# Digital_Part.net
KiCad netlist of a schematic drawn in Altium Designer
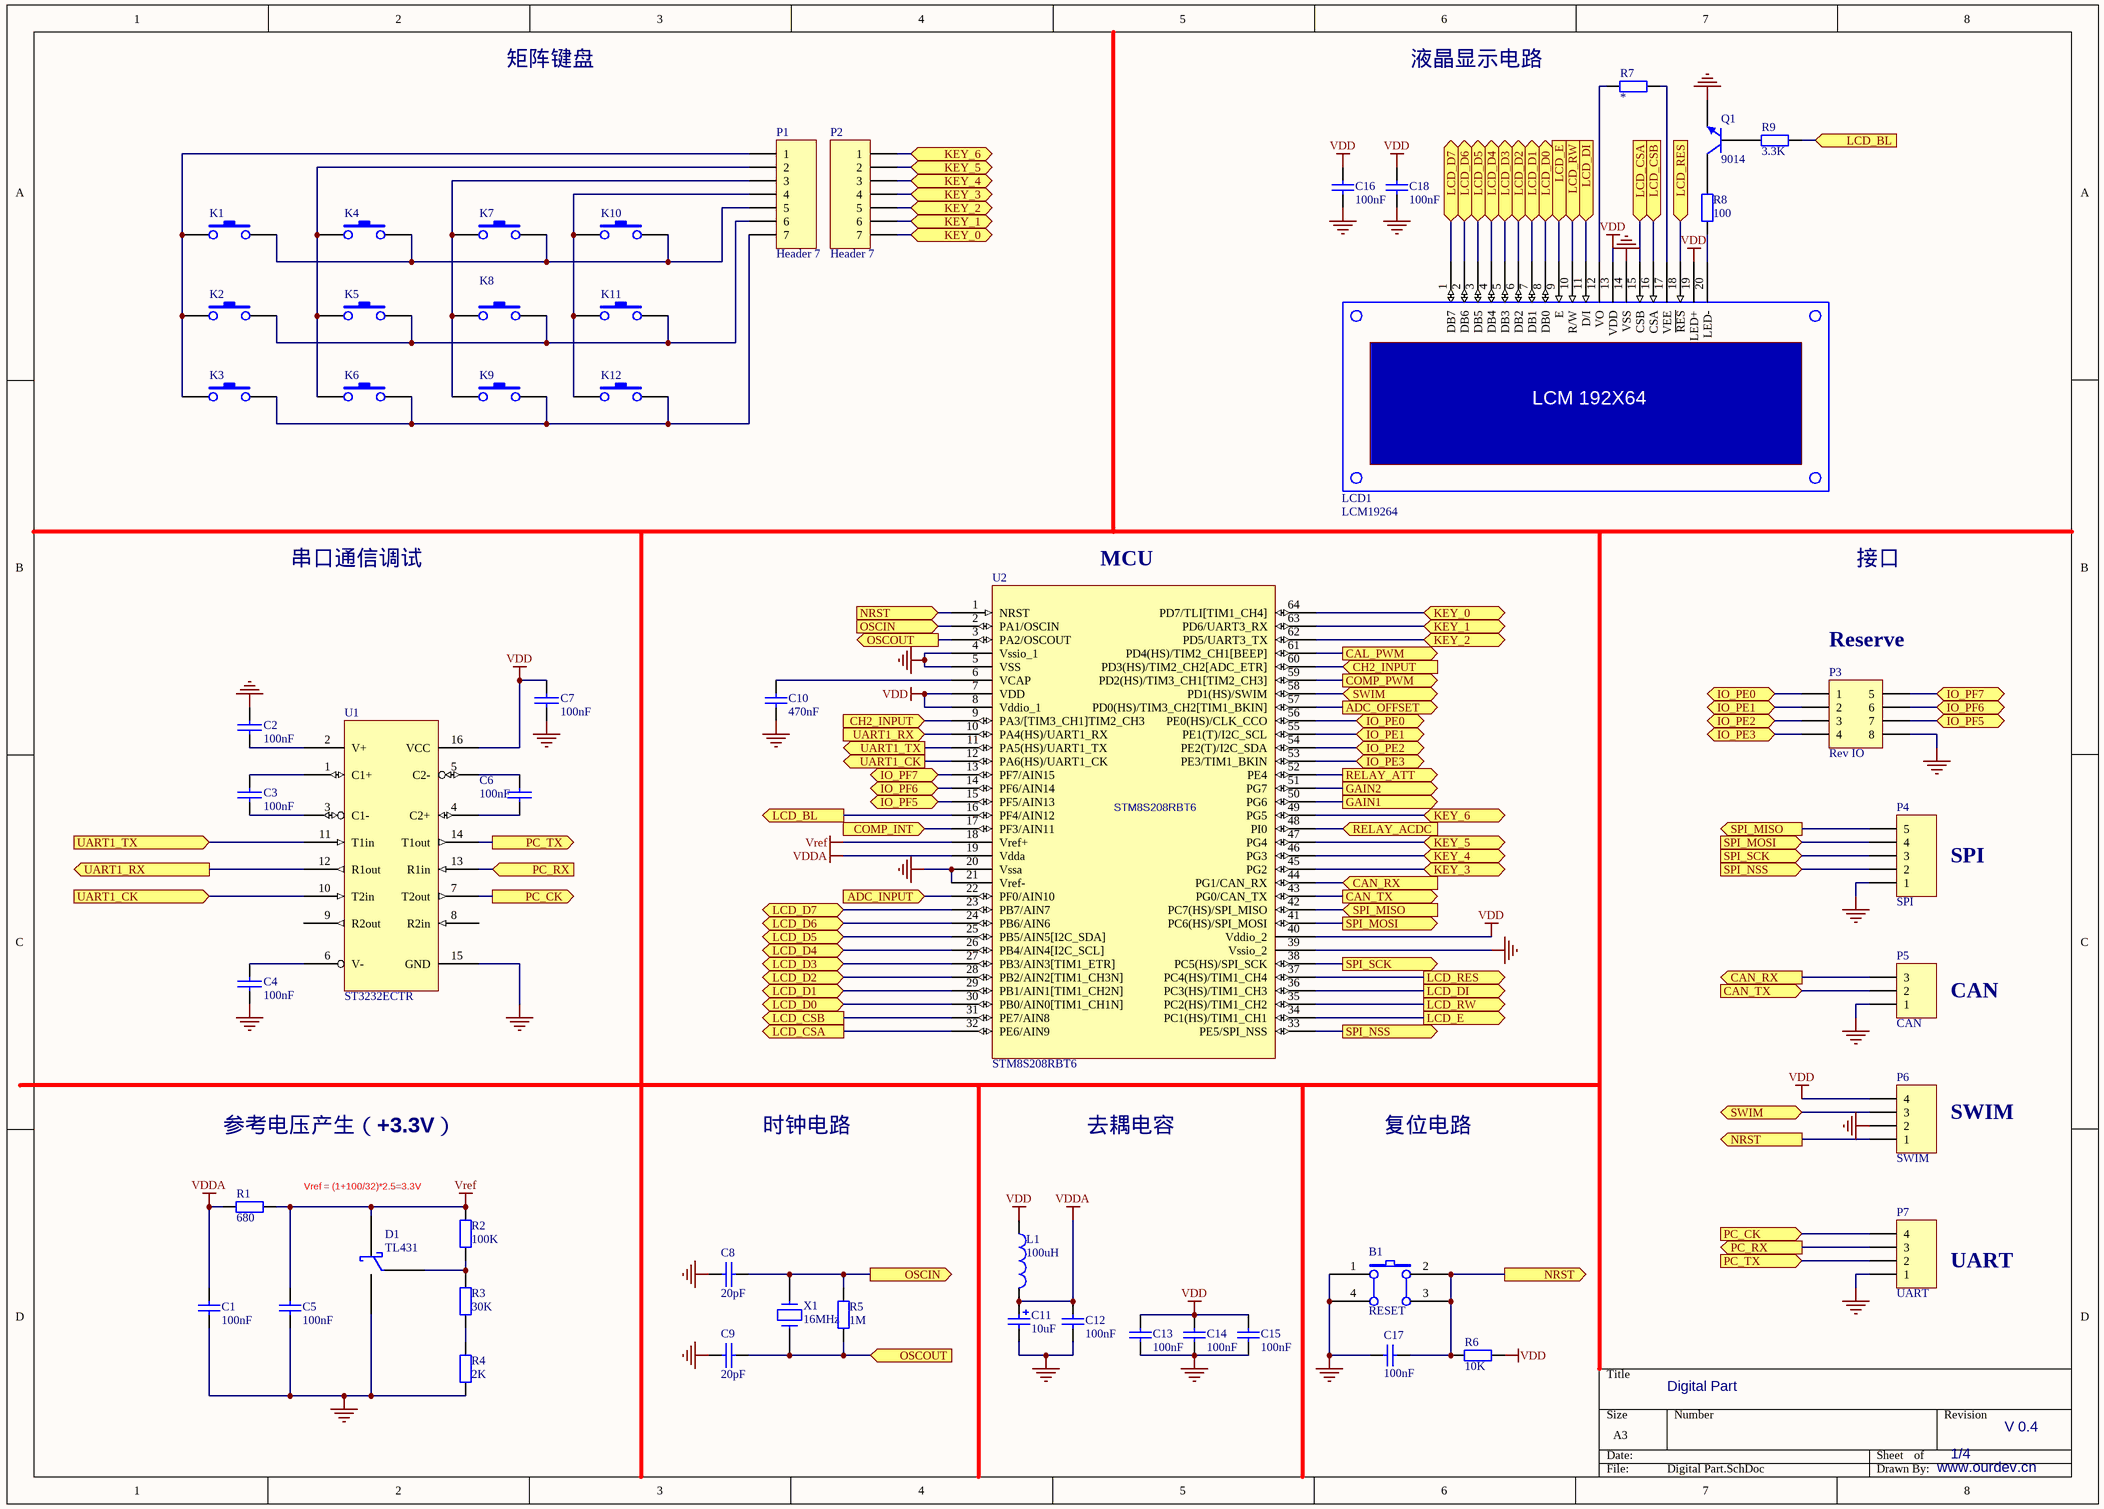
[diagram p0: Digital Part.SchDoc]

(export (version "E")
  (design (tool "Eeschema 10.0.6"))
  (components
    (comp (ref "B1")
      (value "RESET")
      (footprint "PB-2")
      (description "SE PUSHBUTTON")
      (libsource (lib "*") (part "SW PUSHBUTTON"))
    )
    (comp (ref "C1")
      (value "100nF")
      (footprint "CC2012-0805")
      (description "Capacitor")
      (fields (field (name "PUBLISHER") "Altium Limited"))
      (libsource (lib "*") (part "CAP"))
    )
    (comp (ref "C2")
      (value "100nF")
      (footprint "CC2012-0805")
      (description "Capacitor")
      (libsource (lib "") (part "CAP_1"))
    )
    (comp (ref "C3")
      (value "100nF")
      (footprint "CC2012-0805")
      (description "Capacitor")
      (libsource (lib "") (part "CAP_1"))
    )
    (comp (ref "C4")
      (value "100nF")
      (footprint "CC2012-0805")
      (description "Capacitor")
      (libsource (lib "") (part "CAP_1"))
    )
    (comp (ref "C5")
      (value "100nF")
      (footprint "CC2012-0805")
      (description "Capacitor")
      (fields (field (name "PUBLISHER") "Altium Limited"))
      (libsource (lib "*") (part "CAP"))
    )
    (comp (ref "C6")
      (value "100nF")
      (footprint "CC2012-0805")
      (description "Capacitor")
      (libsource (lib "") (part "CAP_1"))
    )
    (comp (ref "C7")
      (value "100nF")
      (footprint "CC2012-0805")
      (description "Capacitor")
      (libsource (lib "") (part "CAP_1"))
    )
    (comp (ref "C8")
      (value "20pF")
      (footprint "CC2012-0805")
      (description "Capacitor")
      (libsource (lib "") (part "CAP_1"))
    )
    (comp (ref "C9")
      (value "20pF")
      (footprint "CC2012-0805")
      (description "Capacitor")
      (libsource (lib "") (part "CAP_1"))
    )
    (comp (ref "C10")
      (value "470nF")
      (footprint "CC2012-0805")
      (description "Capacitor")
      (fields (field (name "PUBLISHER") "Altium Limited"))
      (libsource (lib "*") (part "CAP"))
    )
    (comp (ref "C11")
      (value "10uF")
      (footprint "C-1206")
      (description "Polarized Capacitor (Radial)")
      (fields (field (name "PUBLISHER") "Altium Limited"))
      (libsource (lib "*") (part "Cap Pol1"))
    )
    (comp (ref "C12")
      (value "100nF")
      (footprint "CC2012-0805")
      (description "Capacitor")
      (fields (field (name "PUBLISHER") "Altium Limited"))
      (libsource (lib "*") (part "CAP"))
    )
    (comp (ref "C13")
      (value "100nF")
      (footprint "CC2012-0805")
      (description "Capacitor")
      (fields (field (name "PUBLISHER") "Altium Limited"))
      (libsource (lib "*") (part "CAP"))
    )
    (comp (ref "C14")
      (value "100nF")
      (footprint "CC2012-0805")
      (description "Capacitor")
      (fields (field (name "PUBLISHER") "Altium Limited"))
      (libsource (lib "*") (part "CAP"))
    )
    (comp (ref "C15")
      (value "100nF")
      (footprint "CC2012-0805")
      (description "Capacitor")
      (fields (field (name "PUBLISHER") "Altium Limited"))
      (libsource (lib "*") (part "CAP"))
    )
    (comp (ref "C16")
      (value "100nF")
      (footprint "CC2012-0805")
      (description "Capacitor")
      (fields (field (name "PUBLISHER") "Altium Limited"))
      (libsource (lib "*") (part "CAP"))
    )
    (comp (ref "C17")
      (value "100nF")
      (footprint "CC2012-0805")
      (description "Capacitor")
      (fields (field (name "PUBLISHER") "Altium Limited"))
      (libsource (lib "*") (part "CAP"))
    )
    (comp (ref "C18")
      (value "100nF")
      (footprint "CC2012-0805")
      (description "Capacitor")
      (fields (field (name "PUBLISHER") "Altium Limited"))
      (libsource (lib "*") (part "CAP"))
    )
    (comp (ref "D1") (value "TL431") (footprint "SOT-89") (libsource (lib "TL431") (part "TL431")))
    (comp (ref "K1") (value "~") (footprint "PB-2") (libsource (lib "*") (part "SW-PB")))
    (comp (ref "K2") (value "~") (footprint "PB-2") (libsource (lib "*") (part "SW-PB")))
    (comp (ref "K3") (value "~") (footprint "PB-2") (libsource (lib "*") (part "SW-PB")))
    (comp (ref "K4") (value "~") (footprint "PB-2") (libsource (lib "*") (part "SW-PB")))
    (comp (ref "K5") (value "~") (footprint "PB-2") (libsource (lib "*") (part "SW-PB")))
    (comp (ref "K6") (value "~") (footprint "PB-2") (libsource (lib "*") (part "SW-PB")))
    (comp (ref "K7") (value "~") (footprint "PB-2") (libsource (lib "*") (part "SW-PB")))
    (comp (ref "K8") (value "~") (footprint "PB-2") (libsource (lib "*") (part "SW-PB")))
    (comp (ref "K9") (value "~") (footprint "PB-2") (libsource (lib "*") (part "SW-PB")))
    (comp (ref "K10") (value "~") (footprint "PB-2") (libsource (lib "*") (part "SW-PB")))
    (comp (ref "K11") (value "~") (footprint "PB-2") (libsource (lib "*") (part "SW-PB")))
    (comp (ref "K12") (value "~") (footprint "PB-2") (libsource (lib "*") (part "SW-PB")))
    (comp (ref "L1")
      (value "100uH")
      (footprint "L-1206")
      (description "Inductor")
      (fields (field (name "PUBLISHER") "Altium Limited"))
      (libsource (lib "*") (part "Inductor"))
    )
    (comp (ref "LCD1")
      (value "LCM19264")
      (footprint "HDR2X10")
      (libsource (lib "LCM 19264") (part "LCM19264"))
    )
    (comp (ref "P1")
      (value "Header 7")
      (footprint "HDR1X7")
      (description "Header, 7-Pin")
      (fields (field (name "PUBLISHER") "Altium Limited"))
      (libsource (lib "") (part "Header 7_1"))
    )
    (comp (ref "P2")
      (value "Header 7")
      (footprint "HDR1X7")
      (description "Header, 7-Pin")
      (fields (field (name "PUBLISHER") "Altium Limited"))
      (libsource (lib "Miscellaneous Connectors") (part "Header 7"))
    )
    (comp (ref "P3")
      (value "Rev IO")
      (footprint "HDR2X4_CEN")
      (description "Header, 4-Pin, Dual row")
      (fields (field (name "PUBLISHER") "Altium Limited"))
      (libsource (lib "Miscellaneous Connectors") (part "Header 4X2A"))
    )
    (comp (ref "P4")
      (value "SPI")
      (footprint "HDR1X5")
      (description "Header, 5-Pin")
      (fields (field (name "PUBLISHER") "Altium Limited"))
      (libsource (lib "Miscellaneous Connectors") (part "Header 5"))
    )
    (comp (ref "P5")
      (value "CAN")
      (footprint "HDR1X3")
      (description "Header, 3-Pin")
      (fields (field (name "PUBLISHER") "Altium Limited"))
      (libsource (lib "Miscellaneous Connectors") (part "Header 3"))
    )
    (comp (ref "P6")
      (value "SWIM")
      (footprint "HDR1X4")
      (description "Header, 4-Pin")
      (fields (field (name "PUBLISHER") "Altium Limited"))
      (libsource (lib "Miscellaneous Connectors") (part "Header 4"))
    )
    (comp (ref "P7")
      (value "UART")
      (footprint "HDR1X4")
      (description "Header, 4-Pin")
      (fields (field (name "PUBLISHER") "Altium Limited"))
      (libsource (lib "Miscellaneous Connectors") (part "Header 4"))
    )
    (comp (ref "Q1")
      (value "9014")
      (footprint "SOT-23")
      (description "NPN General Purpose Amplifier")
      (fields (field (name "PUBLISHER") "Altium Limited"))
      (libsource (lib "Miscellaneous Devices") (part "2N3904"))
    )
    (comp (ref "R1")
      (value "680")
      (footprint "CR2012-0805")
      (description "Resistor")
      (fields (field (name "PUBLISHER") "Altium Limited"))
      (libsource (lib "") (part "Res2_2"))
    )
    (comp (ref "R2")
      (value "100K")
      (footprint "CR2012-0805")
      (description "Resistor")
      (fields (field (name "PUBLISHER") "Altium Limited"))
      (libsource (lib "") (part "Res2_1"))
    )
    (comp (ref "R3")
      (value "30K")
      (footprint "CR2012-0805")
      (description "Resistor")
      (fields (field (name "PUBLISHER") "Altium Limited"))
      (libsource (lib "") (part "Res2_1"))
    )
    (comp (ref "R4")
      (value "2K")
      (footprint "CR2012-0805")
      (description "Resistor")
      (fields (field (name "PUBLISHER") "Altium Limited"))
      (libsource (lib "") (part "Res2_1"))
    )
    (comp (ref "R5")
      (value "1M")
      (footprint "CR2012-0805")
      (description "Resistor")
      (fields (field (name "PUBLISHER") "Altium Limited"))
      (libsource (lib "") (part "Res2_3"))
    )
    (comp (ref "R6")
      (value "10K")
      (footprint "CR2012-0805")
      (description "Resistor")
      (fields (field (name "PUBLISHER") "Altium Limited"))
      (libsource (lib "Miscellaneous Devices") (part "Res2"))
    )
    (comp (ref "R7")
      (value "*")
      (footprint "CR2012-0805")
      (description "Resistor")
      (fields (field (name "ALTIUM_VALUE") "*") (field (name "PUBLISHER") "Altium Limited"))
      (libsource (lib "") (part "Res2_2"))
    )
    (comp (ref "R8")
      (value "100")
      (footprint "CR2012-0805")
      (description "Resistor")
      (fields (field (name "Comment") "3.3K") (field (name "PUBLISHER") "Altium Limited"))
      (libsource (lib "") (part "Res2_1"))
    )
    (comp (ref "R9")
      (value "3.3K")
      (footprint "CR2012-0805")
      (description "Resistor")
      (fields (field (name "PUBLISHER") "Altium Limited"))
      (libsource (lib "Miscellaneous Devices") (part "Res2"))
    )
    (comp (ref "U1")
      (value "ST3232ECTR")
      (footprint "SO-16")
      (description "3.3V/5V Dual RS232 Transceiver w/ Int. Cap.")
      (libsource (lib "*") (part "ST3232"))
    )
    (comp (ref "U2")
      (value "STM8S208RBT6")
      (footprint "TQFP-64")
      (libsource (lib "STM8S208RBT6") (part "STM8S208RBT6"))
    )
    (comp (ref "X1")
      (value "16MHz")
      (footprint "CRYSTAL")
      (description "Crystal")
      (libsource (lib "*") (part "CRYSTAL"))
    )
  )
  (nets
    (net (code "1") (name "/ADC_INPUT") (class "Default")
      (node (ref "U2") (pin "22") (pinfunction "PF0/AIN10_22") (pintype "bidirectional"))
    )
    (net (code "2") (name "/ADC_OFFSET") (class "Default")
      (node (ref "U2") (pin "57") (pinfunction "PD0(HS)/TIM3_CH2[TIM1_BKIN]_57") (pintype "bidirectional"))
    )
    (net (code "3") (name "/CAL_PWM") (class "Default")
      (node (ref "U2") (pin "61") (pinfunction "PD4(HS)/TIM2_CH1[BEEP]_61") (pintype "bidirectional"))
    )
    (net (code "4") (name "/CAN_RX") (class "Default")
      (node (ref "P5") (pin "3") (pinfunction "3_3") (pintype "passive"))
      (node (ref "U2") (pin "44") (pinfunction "PG1/CAN_RX_44") (pintype "bidirectional"))
    )
    (net (code "5") (name "/CAN_TX") (class "Default")
      (node (ref "P5") (pin "2") (pinfunction "2_2") (pintype "passive"))
      (node (ref "U2") (pin "43") (pinfunction "PG0/CAN_TX_43") (pintype "bidirectional"))
    )
    (net (code "6") (name "/CH2_INPUT") (class "Default")
      (node (ref "U2") (pin "60") (pinfunction "PD3(HS)/TIM2_CH2[ADC_ETR]_60") (pintype "bidirectional"))
      (node (ref "U2") (pin "9") (pinfunction "PA3/[TIM3_CH1]TIM2_CH3_9") (pintype "bidirectional"))
    )
    (net (code "7") (name "/COMP_INT") (class "Default")
      (node (ref "U2") (pin "17") (pinfunction "PF3/AIN11_17") (pintype "bidirectional"))
    )
    (net (code "8") (name "/COMP_PWM") (class "Default")
      (node (ref "U2") (pin "59") (pinfunction "PD2(HS)/TIM3_CH1[TIM2_CH3]_59") (pintype "bidirectional"))
    )
    (net (code "9") (name "/GAIN1") (class "Default")
      (node (ref "U2") (pin "50") (pinfunction "PG6_50") (pintype "bidirectional"))
    )
    (net (code "10") (name "/GAIN2") (class "Default")
      (node (ref "U2") (pin "51") (pinfunction "PG7_51") (pintype "bidirectional"))
    )
    (net (code "11") (name "/IO_PE0") (class "Default")
      (node (ref "P3") (pin "1") (pinfunction "1_1") (pintype "passive"))
      (node (ref "U2") (pin "56") (pinfunction "PE0(HS)/CLK_CCO_56") (pintype "bidirectional"))
    )
    (net (code "12") (name "/IO_PE1") (class "Default")
      (node (ref "P3") (pin "2") (pinfunction "2_2") (pintype "passive"))
      (node (ref "U2") (pin "55") (pinfunction "PE1(T)/I2C_SCL_55") (pintype "bidirectional"))
    )
    (net (code "13") (name "/IO_PE2") (class "Default")
      (node (ref "P3") (pin "3") (pinfunction "3_3") (pintype "passive"))
      (node (ref "U2") (pin "54") (pinfunction "PE2(T)/I2C_SDA_54") (pintype "bidirectional"))
    )
    (net (code "14") (name "/IO_PE3") (class "Default")
      (node (ref "P3") (pin "4") (pinfunction "4_4") (pintype "passive"))
      (node (ref "U2") (pin "53") (pinfunction "PE3/TIM1_BKIN_53") (pintype "bidirectional"))
    )
    (net (code "15") (name "/IO_PF5") (class "Default")
      (node (ref "P3") (pin "7") (pinfunction "7_7") (pintype "passive"))
      (node (ref "U2") (pin "15") (pinfunction "PF5/AIN13_15") (pintype "bidirectional"))
    )
    (net (code "16") (name "/IO_PF6") (class "Default")
      (node (ref "P3") (pin "6") (pinfunction "6_6") (pintype "passive"))
      (node (ref "U2") (pin "14") (pinfunction "PF6/AIN14_14") (pintype "bidirectional"))
    )
    (net (code "17") (name "/IO_PF7") (class "Default")
      (node (ref "P3") (pin "5") (pinfunction "5_5") (pintype "passive"))
      (node (ref "U2") (pin "13") (pinfunction "PF7/AIN15_13") (pintype "bidirectional"))
    )
    (net (code "18") (name "/KEY_0") (class "Default")
      (node (ref "P2") (pin "7") (pinfunction "7_7") (pintype "passive"))
      (node (ref "U2") (pin "64") (pinfunction "PD7/TLI[TIM1_CH4]_64") (pintype "bidirectional"))
    )
    (net (code "19") (name "/KEY_1") (class "Default")
      (node (ref "P2") (pin "6") (pinfunction "6_6") (pintype "passive"))
      (node (ref "U2") (pin "63") (pinfunction "PD6/UART3_RX_63") (pintype "bidirectional"))
    )
    (net (code "20") (name "/KEY_2") (class "Default")
      (node (ref "P2") (pin "5") (pinfunction "5_5") (pintype "passive"))
      (node (ref "U2") (pin "62") (pinfunction "PD5/UART3_TX_62") (pintype "bidirectional"))
    )
    (net (code "21") (name "/KEY_3") (class "Default")
      (node (ref "P2") (pin "4") (pinfunction "4_4") (pintype "passive"))
      (node (ref "U2") (pin "45") (pinfunction "PG2_45") (pintype "bidirectional"))
    )
    (net (code "22") (name "/KEY_4") (class "Default")
      (node (ref "P2") (pin "3") (pinfunction "3_3") (pintype "passive"))
      (node (ref "U2") (pin "46") (pinfunction "PG3_46") (pintype "bidirectional"))
    )
    (net (code "23") (name "/KEY_5") (class "Default")
      (node (ref "P2") (pin "2") (pinfunction "2_2") (pintype "passive"))
      (node (ref "U2") (pin "47") (pinfunction "PG4_47") (pintype "bidirectional"))
    )
    (net (code "24") (name "/KEY_6") (class "Default")
      (node (ref "P2") (pin "1") (pinfunction "1_1") (pintype "passive"))
      (node (ref "U2") (pin "49") (pinfunction "PG5_49") (pintype "bidirectional"))
    )
    (net (code "25") (name "/LCD_BL") (class "Default")
      (node (ref "R9") (pin "1") (pinfunction "1_1") (pintype "passive"))
      (node (ref "U2") (pin "16") (pinfunction "PF4/AIN12_16") (pintype "bidirectional"))
    )
    (net (code "26") (name "/LCD_CSA") (class "Default")
      (node (ref "LCD1") (pin "15") (pinfunction "CSB_15") (pintype "input"))
      (node (ref "U2") (pin "32") (pinfunction "PE6/AIN9_32") (pintype "bidirectional"))
    )
    (net (code "27") (name "/LCD_CSB") (class "Default")
      (node (ref "LCD1") (pin "16") (pinfunction "CSA_16") (pintype "input"))
      (node (ref "U2") (pin "31") (pinfunction "PE7/AIN8_31") (pintype "bidirectional"))
    )
    (net (code "28") (name "/LCD_D0") (class "Default")
      (node (ref "LCD1") (pin "8") (pinfunction "DB0_8") (pintype "bidirectional"))
      (node (ref "U2") (pin "30") (pinfunction "PB0/AIN0[TIM1_CH1N]_30") (pintype "bidirectional"))
    )
    (net (code "29") (name "/LCD_D1") (class "Default")
      (node (ref "LCD1") (pin "7") (pinfunction "DB1_7") (pintype "bidirectional"))
      (node (ref "U2") (pin "29") (pinfunction "PB1/AIN1[TIM1_CH2N]_29") (pintype "bidirectional"))
    )
    (net (code "30") (name "/LCD_D2") (class "Default")
      (node (ref "LCD1") (pin "6") (pinfunction "DB2_6") (pintype "bidirectional"))
      (node (ref "U2") (pin "28") (pinfunction "PB2/AIN2[TIM1_CH3N]_28") (pintype "bidirectional"))
    )
    (net (code "31") (name "/LCD_D3") (class "Default")
      (node (ref "LCD1") (pin "5") (pinfunction "DB3_5") (pintype "bidirectional"))
      (node (ref "U2") (pin "27") (pinfunction "PB3/AIN3[TIM1_ETR]_27") (pintype "bidirectional"))
    )
    (net (code "32") (name "/LCD_D4") (class "Default")
      (node (ref "LCD1") (pin "4") (pinfunction "DB4_4") (pintype "bidirectional"))
      (node (ref "U2") (pin "26") (pinfunction "PB4/AIN4[I2C_SCL]_26") (pintype "bidirectional"))
    )
    (net (code "33") (name "/LCD_D5") (class "Default")
      (node (ref "LCD1") (pin "3") (pinfunction "DB5_3") (pintype "bidirectional"))
      (node (ref "U2") (pin "25") (pinfunction "PB5/AIN5[I2C_SDA]_25") (pintype "bidirectional"))
    )
    (net (code "34") (name "/LCD_D6") (class "Default")
      (node (ref "LCD1") (pin "2") (pinfunction "DB6_2") (pintype "bidirectional"))
      (node (ref "U2") (pin "24") (pinfunction "PB6/AIN6_24") (pintype "bidirectional"))
    )
    (net (code "35") (name "/LCD_D7") (class "Default")
      (node (ref "LCD1") (pin "1") (pinfunction "DB7_1") (pintype "bidirectional"))
      (node (ref "U2") (pin "23") (pinfunction "PB7/AIN7_23") (pintype "bidirectional"))
    )
    (net (code "36") (name "/LCD_DI") (class "Default")
      (node (ref "LCD1") (pin "11") (pinfunction "D/I_11") (pintype "input"))
      (node (ref "U2") (pin "36") (pinfunction "PC3(HS)/TIM1_CH3_36") (pintype "bidirectional"))
    )
    (net (code "37") (name "/LCD_E") (class "Default")
      (node (ref "LCD1") (pin "9") (pinfunction "E_9") (pintype "input"))
      (node (ref "U2") (pin "34") (pinfunction "PC1(HS)/TIM1_CH1_34") (pintype "bidirectional"))
    )
    (net (code "38") (name "/LCD_RES") (class "Default")
      (node (ref "LCD1") (pin "18") (pinfunction "~{RES}_18") (pintype "input"))
      (node (ref "U2") (pin "37") (pinfunction "PC4(HS)/TIM1_CH4_37") (pintype "bidirectional"))
    )
    (net (code "39") (name "/LCD_RW") (class "Default")
      (node (ref "LCD1") (pin "10") (pinfunction "R/W_10") (pintype "input"))
      (node (ref "U2") (pin "35") (pinfunction "PC2(HS)/TIM1_CH2_35") (pintype "bidirectional"))
    )
    (net (code "40") (name "/NRST") (class "Default")
      (node (ref "B1") (pin "2") (pinfunction "B0_2") (pintype "passive"))
      (node (ref "B1") (pin "3") (pinfunction "B1_3") (pintype "passive"))
      (node (ref "C17") (pin "2") (pinfunction "2_2") (pintype "passive"))
      (node (ref "P6") (pin "1") (pinfunction "1_1") (pintype "passive"))
      (node (ref "R6") (pin "2") (pinfunction "2_2") (pintype "passive"))
      (node (ref "U2") (pin "1") (pinfunction "NRST_1") (pintype "input"))
    )
    (net (code "41") (name "/OSCIN") (class "Default")
      (node (ref "C8") (pin "1") (pinfunction "1_1") (pintype "passive"))
      (node (ref "R5") (pin "2") (pinfunction "2_2") (pintype "passive"))
      (node (ref "U2") (pin "2") (pinfunction "PA1/OSCIN_2") (pintype "bidirectional"))
      (node (ref "X1") (pin "2") (pinfunction "2_2") (pintype "passive"))
    )
    (net (code "42") (name "/OSCOUT") (class "Default")
      (node (ref "C9") (pin "1") (pinfunction "1_1") (pintype "passive"))
      (node (ref "R5") (pin "1") (pinfunction "1_1") (pintype "passive"))
      (node (ref "U2") (pin "3") (pinfunction "PA2/OSCOUT_3") (pintype "bidirectional"))
      (node (ref "X1") (pin "1") (pinfunction "1_1") (pintype "passive"))
    )
    (net (code "43") (name "/PC_CK") (class "Default")
      (node (ref "P7") (pin "4") (pinfunction "4_4") (pintype "passive"))
      (node (ref "U1") (pin "7") (pinfunction "T2out_7") (pintype "output"))
    )
    (net (code "44") (name "/PC_RX") (class "Default")
      (node (ref "P7") (pin "3") (pinfunction "3_3") (pintype "passive"))
      (node (ref "U1") (pin "13") (pinfunction "R1in_13") (pintype "input"))
    )
    (net (code "45") (name "/PC_TX") (class "Default")
      (node (ref "P7") (pin "2") (pinfunction "2_2") (pintype "passive"))
      (node (ref "U1") (pin "14") (pinfunction "T1out_14") (pintype "output"))
    )
    (net (code "46") (name "/RELAY_ACDC") (class "Default")
      (node (ref "U2") (pin "48") (pinfunction "PI0_48") (pintype "bidirectional"))
    )
    (net (code "47") (name "/RELAY_ATT") (class "Default")
      (node (ref "U2") (pin "52") (pinfunction "PE4_52") (pintype "bidirectional"))
    )
    (net (code "48") (name "/SPI_MISO") (class "Default")
      (node (ref "P4") (pin "5") (pinfunction "5_5") (pintype "passive"))
      (node (ref "U2") (pin "42") (pinfunction "PC7(HS)/SPI_MISO_42") (pintype "bidirectional"))
    )
    (net (code "49") (name "/SPI_MOSI") (class "Default")
      (node (ref "P4") (pin "4") (pinfunction "4_4") (pintype "passive"))
      (node (ref "U2") (pin "41") (pinfunction "PC6(HS)/SPI_MOSI_41") (pintype "bidirectional"))
    )
    (net (code "50") (name "/SPI_NSS") (class "Default")
      (node (ref "P4") (pin "2") (pinfunction "2_2") (pintype "passive"))
      (node (ref "U2") (pin "33") (pinfunction "PE5/SPI_NSS_33") (pintype "bidirectional"))
    )
    (net (code "51") (name "/SPI_SCK") (class "Default")
      (node (ref "P4") (pin "3") (pinfunction "3_3") (pintype "passive"))
      (node (ref "U2") (pin "38") (pinfunction "PC5(HS)/SPI_SCK_38") (pintype "bidirectional"))
    )
    (net (code "52") (name "/SWIM") (class "Default")
      (node (ref "P6") (pin "3") (pinfunction "3_3") (pintype "passive"))
      (node (ref "U2") (pin "58") (pinfunction "PD1(HS)/SWIM_58") (pintype "bidirectional"))
    )
    (net (code "53") (name "/UART1_CK") (class "Default")
      (node (ref "U1") (pin "10") (pinfunction "T2in_10") (pintype "input"))
      (node (ref "U2") (pin "12") (pinfunction "PA6(HS)/UART1_CK_12") (pintype "bidirectional"))
    )
    (net (code "54") (name "/UART1_RX") (class "Default")
      (node (ref "U1") (pin "12") (pinfunction "R1out_12") (pintype "output"))
      (node (ref "U2") (pin "10") (pinfunction "PA4(HS)/UART1_RX_10") (pintype "bidirectional"))
    )
    (net (code "55") (name "/UART1_TX") (class "Default")
      (node (ref "U1") (pin "11") (pinfunction "T1in_11") (pintype "input"))
      (node (ref "U2") (pin "11") (pinfunction "PA5(HS)/UART1_TX_11") (pintype "bidirectional"))
    )
    (net (code "56") (name "GND") (class "Default")
      (node (ref "B1") (pin "1") (pinfunction "A0_1") (pintype "passive"))
      (node (ref "B1") (pin "4") (pinfunction "A1_4") (pintype "passive"))
      (node (ref "C1") (pin "2") (pinfunction "2_2") (pintype "passive"))
      (node (ref "C10") (pin "1") (pinfunction "1_1") (pintype "passive"))
      (node (ref "C11") (pin "2") (pinfunction "1_2") (pintype "passive"))
      (node (ref "C12") (pin "2") (pinfunction "2_2") (pintype "passive"))
      (node (ref "C13") (pin "2") (pinfunction "2_2") (pintype "passive"))
      (node (ref "C14") (pin "2") (pinfunction "2_2") (pintype "passive"))
      (node (ref "C15") (pin "2") (pinfunction "2_2") (pintype "passive"))
      (node (ref "C16") (pin "2") (pinfunction "2_2") (pintype "passive"))
      (node (ref "C17") (pin "1") (pinfunction "1_1") (pintype "passive"))
      (node (ref "C18") (pin "2") (pinfunction "2_2") (pintype "passive"))
      (node (ref "C2") (pin "1") (pinfunction "1_1") (pintype "passive"))
      (node (ref "C4") (pin "1") (pinfunction "1_1") (pintype "passive"))
      (node (ref "C5") (pin "2") (pinfunction "2_2") (pintype "passive"))
      (node (ref "C7") (pin "2") (pinfunction "2_2") (pintype "passive"))
      (node (ref "C8") (pin "2") (pinfunction "2_2") (pintype "passive"))
      (node (ref "C9") (pin "2") (pinfunction "2_2") (pintype "passive"))
      (node (ref "D1") (pin "2") (pinfunction "ANODE_2") (pintype "passive"))
      (node (ref "LCD1") (pin "14") (pinfunction "VSS_14") (pintype "power_in"))
      (node (ref "P3") (pin "8") (pinfunction "8_8") (pintype "passive"))
      (node (ref "P4") (pin "1") (pinfunction "1_1") (pintype "passive"))
      (node (ref "P5") (pin "1") (pinfunction "1_1") (pintype "passive"))
      (node (ref "P6") (pin "2") (pinfunction "2_2") (pintype "passive"))
      (node (ref "P7") (pin "1") (pinfunction "1_1") (pintype "passive"))
      (node (ref "Q1") (pin "2") (pinfunction "E_2") (pintype "passive"))
      (node (ref "R4") (pin "2") (pinfunction "2_2") (pintype "passive"))
      (node (ref "U1") (pin "15") (pinfunction "GND_15") (pintype "passive"))
      (node (ref "U2") (pin "20") (pinfunction "Vssa_20") (pintype "power_in"))
      (node (ref "U2") (pin "21") (pinfunction "Vref-_21") (pintype "power_in"))
      (node (ref "U2") (pin "39") (pinfunction "Vssio_2_39") (pintype "power_in"))
      (node (ref "U2") (pin "4") (pinfunction "Vssio_1_4") (pintype "power_in"))
      (node (ref "U2") (pin "5") (pinfunction "VSS_5") (pintype "power_in"))
    )
    (net (code "57") (name "Net-(D1-REF)") (class "Default")
      (node (ref "D1") (pin "1") (pinfunction "REF_1") (pintype "passive"))
      (node (ref "R2") (pin "2") (pinfunction "2_2") (pintype "passive"))
      (node (ref "R3") (pin "1") (pinfunction "1_1") (pintype "passive"))
    )
    (net (code "58") (name "Net-(K1-Pad1)") (class "Default")
      (node (ref "K1") (pin "1") (pinfunction "1_1") (pintype "passive"))
      (node (ref "K2") (pin "1") (pinfunction "1_1") (pintype "passive"))
      (node (ref "K3") (pin "1") (pinfunction "1_1") (pintype "passive"))
      (node (ref "P1") (pin "1") (pinfunction "1_1") (pintype "passive"))
    )
    (net (code "59") (name "Net-(K1-Pad2)") (class "Default")
      (node (ref "K1") (pin "2") (pinfunction "2_2") (pintype "passive"))
      (node (ref "K10") (pin "2") (pinfunction "2_2") (pintype "passive"))
      (node (ref "K4") (pin "2") (pinfunction "2_2") (pintype "passive"))
      (node (ref "K7") (pin "2") (pinfunction "2_2") (pintype "passive"))
      (node (ref "P1") (pin "5") (pinfunction "5_5") (pintype "passive"))
    )
    (net (code "60") (name "Net-(K4-Pad1)") (class "Default")
      (node (ref "K4") (pin "1") (pinfunction "1_1") (pintype "passive"))
      (node (ref "K5") (pin "1") (pinfunction "1_1") (pintype "passive"))
      (node (ref "K6") (pin "1") (pinfunction "1_1") (pintype "passive"))
      (node (ref "P1") (pin "2") (pinfunction "2_2") (pintype "passive"))
    )
    (net (code "61") (name "Net-(K7-Pad1)") (class "Default")
      (node (ref "K7") (pin "1") (pinfunction "1_1") (pintype "passive"))
      (node (ref "K8") (pin "1") (pinfunction "1_1") (pintype "passive"))
      (node (ref "K9") (pin "1") (pinfunction "1_1") (pintype "passive"))
      (node (ref "P1") (pin "3") (pinfunction "3_3") (pintype "passive"))
    )
    (net (code "62") (name "Net-(K10-Pad1)") (class "Default")
      (node (ref "K10") (pin "1") (pinfunction "1_1") (pintype "passive"))
      (node (ref "K11") (pin "1") (pinfunction "1_1") (pintype "passive"))
      (node (ref "K12") (pin "1") (pinfunction "1_1") (pintype "passive"))
      (node (ref "P1") (pin "4") (pinfunction "4_4") (pintype "passive"))
    )
    (net (code "63") (name "Net-(K11-Pad2)") (class "Default")
      (node (ref "K11") (pin "2") (pinfunction "2_2") (pintype "passive"))
      (node (ref "K2") (pin "2") (pinfunction "2_2") (pintype "passive"))
      (node (ref "K5") (pin "2") (pinfunction "2_2") (pintype "passive"))
      (node (ref "K8") (pin "2") (pinfunction "2_2") (pintype "passive"))
      (node (ref "P1") (pin "6") (pinfunction "6_6") (pintype "passive"))
    )
    (net (code "64") (name "Net-(K12-Pad2)") (class "Default")
      (node (ref "K12") (pin "2") (pinfunction "2_2") (pintype "passive"))
      (node (ref "K3") (pin "2") (pinfunction "2_2") (pintype "passive"))
      (node (ref "K6") (pin "2") (pinfunction "2_2") (pintype "passive"))
      (node (ref "K9") (pin "2") (pinfunction "2_2") (pintype "passive"))
      (node (ref "P1") (pin "7") (pinfunction "7_7") (pintype "passive"))
    )
    (net (code "65") (name "Net-(LCD1-LED-)") (class "Default")
      (node (ref "LCD1") (pin "20") (pinfunction "LED-_20") (pintype "power_in"))
      (node (ref "R8") (pin "2") (pinfunction "2_2") (pintype "passive"))
    )
    (net (code "66") (name "Net-(LCD1-VEE)") (class "Default")
      (node (ref "LCD1") (pin "17") (pinfunction "VEE_17") (pintype "power_in"))
      (node (ref "R7") (pin "2") (pinfunction "2_2") (pintype "passive"))
    )
    (net (code "67") (name "Net-(LCD1-VO)") (class "Default")
      (node (ref "LCD1") (pin "12") (pinfunction "VO_12") (pintype "passive"))
      (node (ref "R7") (pin "1") (pinfunction "1_1") (pintype "passive"))
    )
    (net (code "68") (name "Net-(Q1-B)") (class "Default")
      (node (ref "Q1") (pin "1") (pinfunction "B_1") (pintype "passive"))
      (node (ref "R9") (pin "2") (pinfunction "2_2") (pintype "passive"))
    )
    (net (code "69") (name "Net-(Q1-C)") (class "Default")
      (node (ref "Q1") (pin "3") (pinfunction "C_3") (pintype "passive"))
      (node (ref "R8") (pin "1") (pinfunction "1_1") (pintype "passive"))
    )
    (net (code "70") (name "Net-(R3-Pad2)") (class "Default")
      (node (ref "R3") (pin "2") (pinfunction "2_2") (pintype "passive"))
      (node (ref "R4") (pin "1") (pinfunction "1_1") (pintype "passive"))
    )
    (net (code "71") (name "Net-(U1-C1+)") (class "Default")
      (node (ref "C3") (pin "1") (pinfunction "1_1") (pintype "passive"))
      (node (ref "U1") (pin "1") (pinfunction "C1+_1") (pintype "bidirectional"))
    )
    (net (code "72") (name "Net-(U1-C1-)") (class "Default")
      (node (ref "C3") (pin "2") (pinfunction "2_2") (pintype "passive"))
      (node (ref "U1") (pin "3") (pinfunction "C1-_3") (pintype "bidirectional"))
    )
    (net (code "73") (name "Net-(U1-C2+)") (class "Default")
      (node (ref "C6") (pin "1") (pinfunction "1_1") (pintype "passive"))
      (node (ref "U1") (pin "4") (pinfunction "C2+_4") (pintype "bidirectional"))
    )
    (net (code "74") (name "Net-(U1-C2-)") (class "Default")
      (node (ref "C6") (pin "2") (pinfunction "2_2") (pintype "passive"))
      (node (ref "U1") (pin "5") (pinfunction "C2-_5") (pintype "bidirectional"))
    )
    (net (code "75") (name "Net-(U1-V+)") (class "Default")
      (node (ref "C2") (pin "2") (pinfunction "2_2") (pintype "passive"))
      (node (ref "U1") (pin "2") (pinfunction "V+_2") (pintype "passive"))
    )
    (net (code "76") (name "Net-(U1-V-)") (class "Default")
      (node (ref "C4") (pin "2") (pinfunction "2_2") (pintype "passive"))
      (node (ref "U1") (pin "6") (pinfunction "V-_6") (pintype "passive"))
    )
    (net (code "77") (name "Net-(U2-VCAP)") (class "Default")
      (node (ref "C10") (pin "2") (pinfunction "2_2") (pintype "passive"))
      (node (ref "U2") (pin "6") (pinfunction "VCAP_6") (pintype "power_in"))
    )
    (net (code "78") (name "VDD") (class "Default")
      (node (ref "C13") (pin "1") (pinfunction "1_1") (pintype "passive"))
      (node (ref "C14") (pin "1") (pinfunction "1_1") (pintype "passive"))
      (node (ref "C15") (pin "1") (pinfunction "1_1") (pintype "passive"))
      (node (ref "C16") (pin "1") (pinfunction "1_1") (pintype "passive"))
      (node (ref "C18") (pin "1") (pinfunction "1_1") (pintype "passive"))
      (node (ref "C7") (pin "1") (pinfunction "1_1") (pintype "passive"))
      (node (ref "L1") (pin "1") (pinfunction "1_1") (pintype "passive"))
      (node (ref "LCD1") (pin "13") (pinfunction "VDD_13") (pintype "power_in"))
      (node (ref "LCD1") (pin "19") (pinfunction "LED+_19") (pintype "power_in"))
      (node (ref "P6") (pin "4") (pinfunction "4_4") (pintype "passive"))
      (node (ref "R6") (pin "1") (pinfunction "1_1") (pintype "passive"))
      (node (ref "U1") (pin "16") (pinfunction "VCC_16") (pintype "passive"))
      (node (ref "U2") (pin "40") (pinfunction "Vddio_2_40") (pintype "power_in"))
      (node (ref "U2") (pin "7") (pinfunction "VDD_7") (pintype "power_in"))
      (node (ref "U2") (pin "8") (pinfunction "Vddio_1_8") (pintype "power_in"))
    )
    (net (code "79") (name "VDDA") (class "Default")
      (node (ref "C1") (pin "1") (pinfunction "1_1") (pintype "passive"))
      (node (ref "C11") (pin "1") (pinfunction "2_1") (pintype "passive"))
      (node (ref "C12") (pin "1") (pinfunction "1_1") (pintype "passive"))
      (node (ref "L1") (pin "2") (pinfunction "2_2") (pintype "passive"))
      (node (ref "R1") (pin "1") (pinfunction "1_1") (pintype "passive"))
      (node (ref "U2") (pin "19") (pinfunction "Vdda_19") (pintype "power_in"))
    )
    (net (code "80") (name "Vref") (class "Default")
      (node (ref "C5") (pin "1") (pinfunction "1_1") (pintype "passive"))
      (node (ref "D1") (pin "3") (pinfunction "CATHODE_3") (pintype "passive"))
      (node (ref "R1") (pin "2") (pinfunction "2_2") (pintype "passive"))
      (node (ref "R2") (pin "1") (pinfunction "1_1") (pintype "passive"))
      (node (ref "U2") (pin "18") (pinfunction "Vref+_18") (pintype "power_in"))
    )
    (net (code "81") (name "unconnected-(U1-R2in-Pad8)") (class "Default")
      (node (ref "U1") (pin "8") (pinfunction "R2in_8") (pintype "input"))
    )
    (net (code "82") (name "unconnected-(U1-R2out-Pad9)") (class "Default")
      (node (ref "U1") (pin "9") (pinfunction "R2out_9") (pintype "output"))
    )
  )
)
